# Capacitive_Moisture_Sensor_REV_2.net
KiCad netlist of a schematic drawn in EAGLE
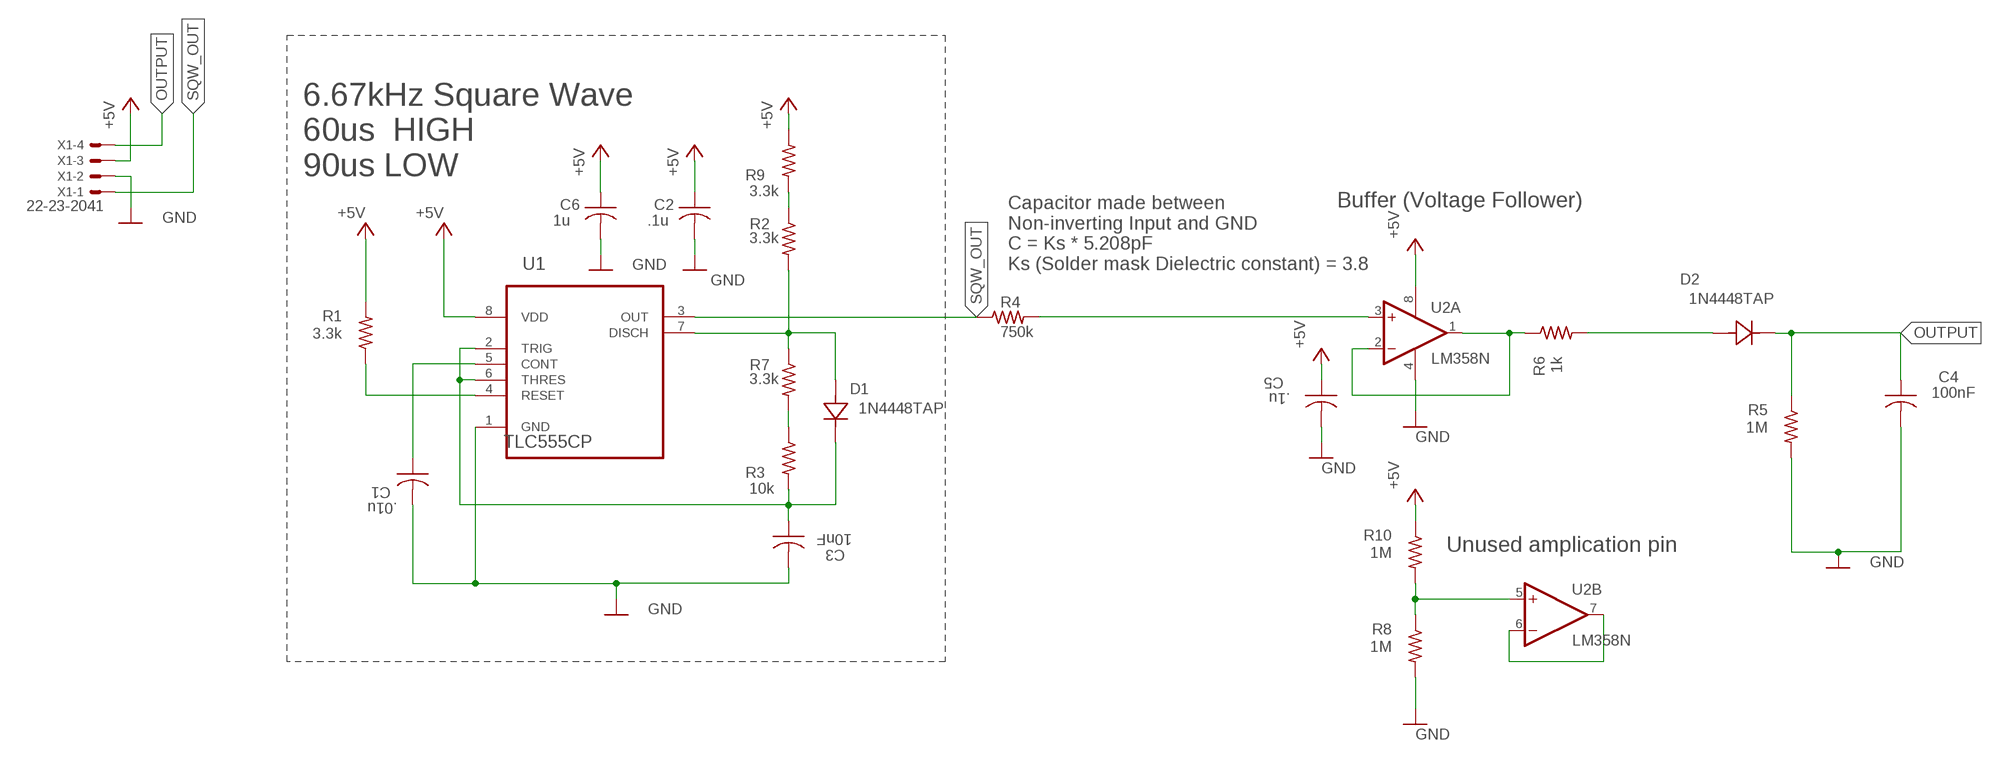
[diagram p0: schematic, sheet 1]

(export (version "E")
  (design (tool "Eeschema 10.0.6"))
  (components
    (comp (ref "C1")
      (value ".01u")
      (footprint "eagle-import:C1206")
      (libsource (lib "eagle-import") (part "C-USC1206"))
    )
    (comp (ref "C2")
      (value ".1u")
      (footprint "eagle-import:C1206")
      (libsource (lib "eagle-import") (part "C-USC1206"))
    )
    (comp (ref "C3")
      (value "10nF")
      (footprint "eagle-import:C1206")
      (libsource (lib "eagle-import") (part "C-USC1206"))
    )
    (comp (ref "C4")
      (value "100nF")
      (footprint "eagle-import:C1206")
      (libsource (lib "eagle-import") (part "C-USC1206"))
    )
    (comp (ref "C5")
      (value ".1u")
      (footprint "eagle-import:C1206")
      (libsource (lib "eagle-import") (part "C-USC1206"))
    )
    (comp (ref "C6")
      (value "1u")
      (footprint "eagle-import:C1206")
      (libsource (lib "eagle-import") (part "C-USC1206"))
    )
    (comp (ref "D1")
      (value "1N4448TAP")
      (footprint "eagle-import:DO-35")
      (libsource (lib "eagle-import") (part "1N4448TAP"))
    )
    (comp (ref "D2")
      (value "1N4448TAP")
      (footprint "eagle-import:DO-35")
      (libsource (lib "eagle-import") (part "1N4448TAP"))
    )
    (comp (ref "R1")
      (value "3.3k")
      (footprint "eagle-import:R1206")
      (libsource (lib "eagle-import") (part "R-US_R1206"))
    )
    (comp (ref "R2")
      (value "3.3k")
      (footprint "eagle-import:R1206")
      (libsource (lib "eagle-import") (part "R-US_R1206"))
    )
    (comp (ref "R3")
      (value "10k")
      (footprint "eagle-import:R1206")
      (libsource (lib "eagle-import") (part "R-US_R1206"))
    )
    (comp (ref "R4")
      (value "750k")
      (footprint "eagle-import:R1206")
      (libsource (lib "eagle-import") (part "R-US_R1206"))
    )
    (comp (ref "R5")
      (value "1M")
      (footprint "eagle-import:R1206")
      (libsource (lib "eagle-import") (part "R-US_R1206"))
    )
    (comp (ref "R6")
      (value "1k")
      (footprint "eagle-import:R1206")
      (libsource (lib "eagle-import") (part "R-US_R1206"))
    )
    (comp (ref "R7")
      (value "3.3k")
      (footprint "eagle-import:R1206")
      (libsource (lib "eagle-import") (part "R-US_R1206"))
    )
    (comp (ref "R8")
      (value "1M")
      (footprint "eagle-import:R1206")
      (libsource (lib "eagle-import") (part "R-US_R1206"))
    )
    (comp (ref "R9")
      (value "3.3k")
      (footprint "eagle-import:R1206")
      (libsource (lib "eagle-import") (part "R-US_R1206"))
    )
    (comp (ref "R10")
      (value "1M")
      (footprint "eagle-import:R1206")
      (libsource (lib "eagle-import") (part "R-US_R1206"))
    )
    (comp (ref "U1")
      (value "TLC555CP")
      (footprint "eagle-import:DIP254P762X508-8")
      (fields (field (name "MF") "Texas Instruments"))
      (libsource (lib "eagle-import") (part "TLC555CP"))
    )
    (comp (ref "U2")
      (value "LM358N")
      (footprint "eagle-import:DIL08")
      (libsource (lib "eagle-import") (part "LM358N"))
    )
    (comp (ref "X1")
      (value "22-23-2041")
      (footprint "eagle-import:22-23-2041")
      (fields (field (name "MF") "MOLEX"))
      (libsource (lib "eagle-import") (part "22-23-2041"))
    )
  )
  (nets
    (net (code "1") (name "+5V") (class "Default")
      (node (ref "C2") (pin "1") (pinfunction "1_1") (pintype "passive"))
      (node (ref "C5") (pin "1") (pinfunction "1_1") (pintype "passive"))
      (node (ref "C6") (pin "1") (pinfunction "1_1") (pintype "passive"))
      (node (ref "R1") (pin "2") (pinfunction "2_2") (pintype "passive"))
      (node (ref "R10") (pin "1") (pinfunction "1_1") (pintype "passive"))
      (node (ref "R9") (pin "1") (pinfunction "1_1") (pintype "passive"))
      (node (ref "U1") (pin "8") (pinfunction "VDD_8") (pintype "power_in"))
      (node (ref "U2") (pin "8") (pinfunction "V+_8") (pintype "power_in"))
      (node (ref "X1") (pin "3") (pinfunction "S_3") (pintype "passive"))
    )
    (net (code "2") (name "GND") (class "Default")
      (node (ref "C1") (pin "2") (pinfunction "2_2") (pintype "passive"))
      (node (ref "C2") (pin "2") (pinfunction "2_2") (pintype "passive"))
      (node (ref "C3") (pin "2") (pinfunction "2_2") (pintype "passive"))
      (node (ref "C4") (pin "2") (pinfunction "2_2") (pintype "passive"))
      (node (ref "C5") (pin "2") (pinfunction "2_2") (pintype "passive"))
      (node (ref "C6") (pin "2") (pinfunction "2_2") (pintype "passive"))
      (node (ref "R5") (pin "2") (pinfunction "2_2") (pintype "passive"))
      (node (ref "R8") (pin "2") (pinfunction "2_2") (pintype "passive"))
      (node (ref "U1") (pin "1") (pinfunction "GND_1") (pintype "passive"))
      (node (ref "U2") (pin "4") (pinfunction "V-_4") (pintype "power_in"))
      (node (ref "X1") (pin "2") (pinfunction "S_2") (pintype "passive"))
    )
    (net (code "3") (name "Net-(D2-Pad2)") (class "Default")
      (node (ref "D2") (pin "2") (pinfunction "2_2") (pintype "passive"))
      (node (ref "R6") (pin "2") (pinfunction "2_2") (pintype "passive"))
    )
    (net (code "4") (name "Net-(R2-Pad1)") (class "Default")
      (node (ref "R2") (pin "1") (pinfunction "1_1") (pintype "passive"))
      (node (ref "R9") (pin "2") (pinfunction "2_2") (pintype "passive"))
    )
    (net (code "5") (name "Net-(R3-Pad1)") (class "Default")
      (node (ref "R3") (pin "1") (pinfunction "1_1") (pintype "passive"))
      (node (ref "R7") (pin "2") (pinfunction "2_2") (pintype "passive"))
    )
    (net (code "6") (name "Net-(U1-CONT)") (class "Default")
      (node (ref "C1") (pin "1") (pinfunction "1_1") (pintype "passive"))
      (node (ref "U1") (pin "5") (pinfunction "CONT_5") (pintype "input"))
    )
    (net (code "7") (name "Net-(U1-DISCH)") (class "Default")
      (node (ref "D1") (pin "2") (pinfunction "2_2") (pintype "passive"))
      (node (ref "R2") (pin "2") (pinfunction "2_2") (pintype "passive"))
      (node (ref "R7") (pin "1") (pinfunction "1_1") (pintype "passive"))
      (node (ref "U1") (pin "7") (pinfunction "DISCH_7") (pintype "output"))
    )
    (net (code "8") (name "Net-(U1-RESET)") (class "Default")
      (node (ref "R1") (pin "1") (pinfunction "1_1") (pintype "passive"))
      (node (ref "U1") (pin "4") (pinfunction "RESET_4") (pintype "input"))
    )
    (net (code "9") (name "Net-(U1-THRES)") (class "Default")
      (node (ref "C3") (pin "1") (pinfunction "1_1") (pintype "passive"))
      (node (ref "D1") (pin "1") (pinfunction "1_1") (pintype "passive"))
      (node (ref "R3") (pin "2") (pinfunction "2_2") (pintype "passive"))
      (node (ref "U1") (pin "2") (pinfunction "TRIG_2") (pintype "input"))
      (node (ref "U1") (pin "6") (pinfunction "THRES_6") (pintype "input"))
    )
    (net (code "10") (name "Net-(U2A-+IN)") (class "Default")
      (node (ref "R4") (pin "2") (pinfunction "2_2") (pintype "passive"))
      (node (ref "U2") (pin "3") (pinfunction "+IN_3") (pintype "input"))
    )
    (net (code "11") (name "Net-(U2A--IN)") (class "Default")
      (node (ref "R6") (pin "1") (pinfunction "1_1") (pintype "passive"))
      (node (ref "U2") (pin "1") (pinfunction "OUT_1") (pintype "output"))
      (node (ref "U2") (pin "2") (pinfunction "-IN_2") (pintype "input"))
    )
    (net (code "12") (name "Net-(U2B-+IN)") (class "Default")
      (node (ref "R10") (pin "2") (pinfunction "2_2") (pintype "passive"))
      (node (ref "R8") (pin "1") (pinfunction "1_1") (pintype "passive"))
      (node (ref "U2") (pin "5") (pinfunction "+IN_5") (pintype "input"))
    )
    (net (code "13") (name "Net-(U2B--IN)") (class "Default")
      (node (ref "U2") (pin "6") (pinfunction "-IN_6") (pintype "input"))
      (node (ref "U2") (pin "7") (pinfunction "OUT_7") (pintype "output"))
    )
    (net (code "14") (name "OUTPUT") (class "Default")
      (node (ref "C4") (pin "1") (pinfunction "1_1") (pintype "passive"))
      (node (ref "D2") (pin "1") (pinfunction "1_1") (pintype "passive"))
      (node (ref "R5") (pin "1") (pinfunction "1_1") (pintype "passive"))
      (node (ref "X1") (pin "4") (pinfunction "S_4") (pintype "passive"))
    )
    (net (code "15") (name "SQW_OUT") (class "Default")
      (node (ref "R4") (pin "1") (pinfunction "1_1") (pintype "passive"))
      (node (ref "U1") (pin "3") (pinfunction "OUT_3") (pintype "output"))
      (node (ref "X1") (pin "1") (pinfunction "S_1") (pintype "passive"))
    )
  )
)
